# NAPaC.net
KiCad netlist of a schematic drawn in Altium Designer
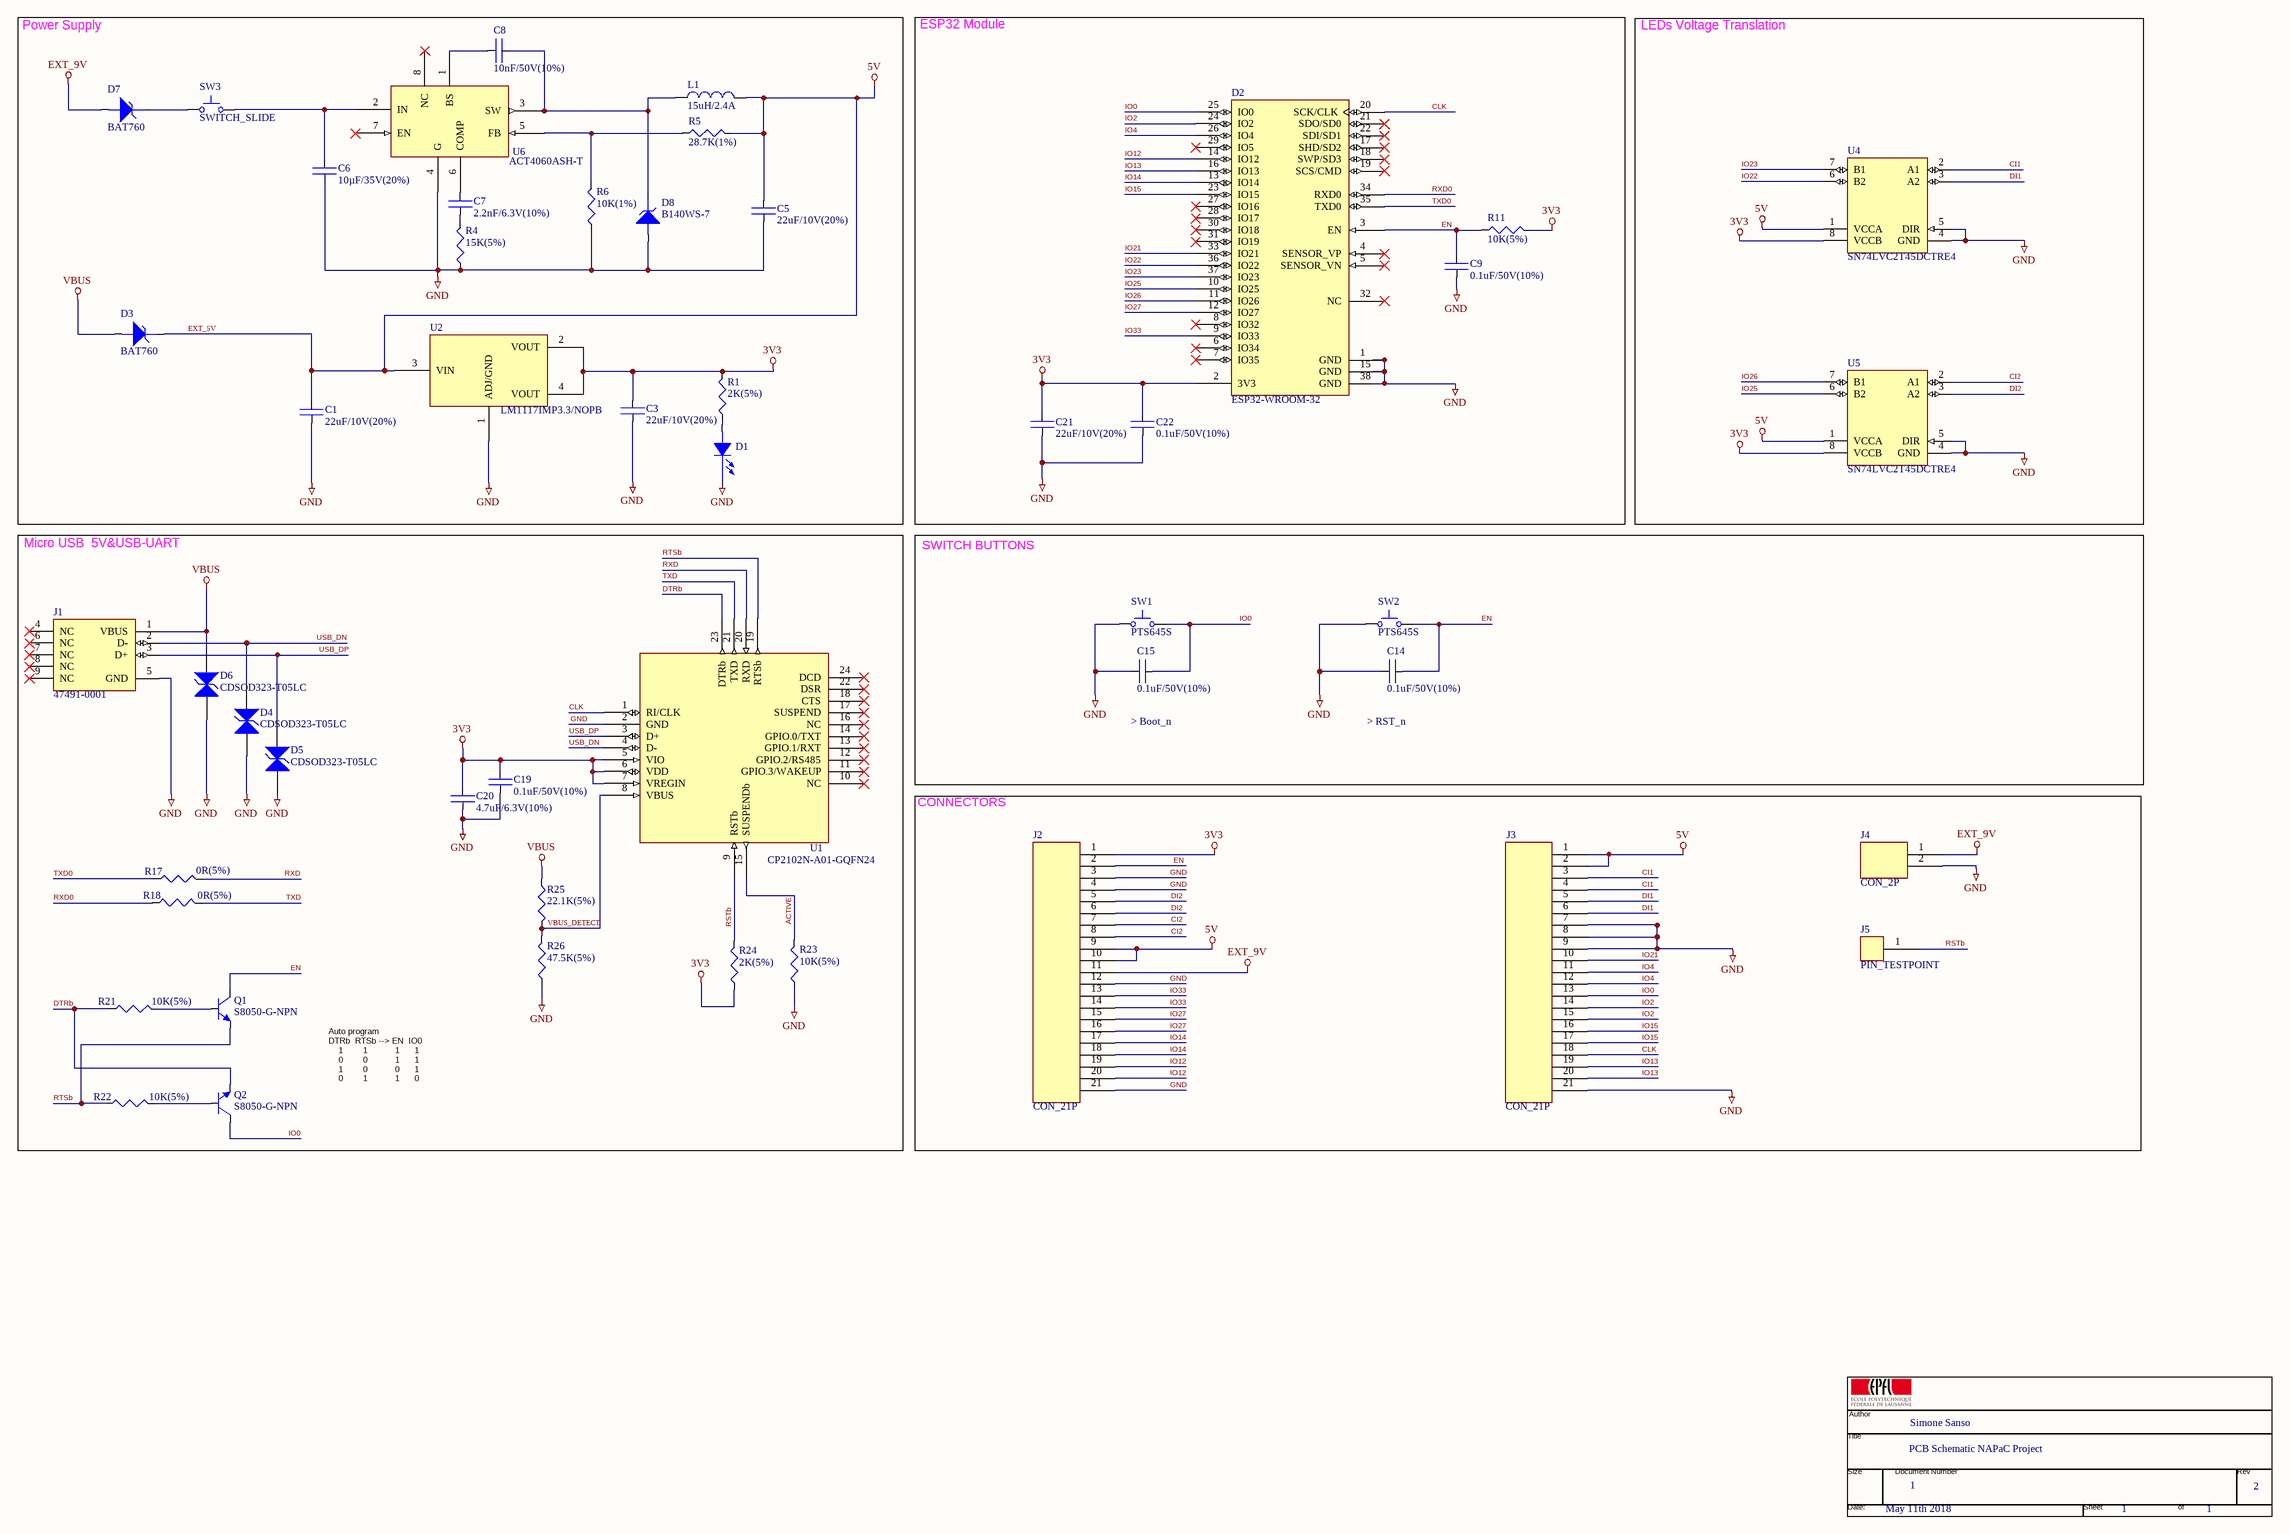
[diagram p0: NAPaC.SchDoc]

(export (version "E")
  (design (tool "Eeschema 10.0.6"))
  (components
    (comp (ref "*") (value "TITLE_BLOCK") (libsource (lib "NAPaC_Schlib") (part "TITLE_BLOCK")))
    (comp (ref "C1")
      (value "22uF/10V(20%)")
      (footprint "CAPC0603")
      (description "GRM188R61A226ME15D-22uF/10V(20%)")
      (libsource (lib "NAPaC_Schlib") (part "CAP-22uF/10V(20%)"))
    )
    (comp (ref "C3")
      (value "22uF/10V(20%)")
      (footprint "CAPC0603")
      (description "GRM188R61A226ME15D-22uF/10V(20%)")
      (libsource (lib "NAPaC_Schlib") (part "CAP-22uF/10V(20%)"))
    )
    (comp (ref "C5")
      (value "22uF/10V(20%)")
      (footprint "CAPC0603")
      (description "GRM188R61A226ME15D-22uF/10V(20%)")
      (libsource (lib "NAPaC_Schlib") (part "CAP-22uF/10V(20%)"))
    )
    (comp (ref "C6")
      (value "10µF/35V(20%)")
      (footprint "CAPC0603")
      (description "C0603C106M8PACTU")
      (libsource (lib "NAPaC_Schlib") (part "CAP-10µF/35V(20%)"))
    )
    (comp (ref "C7")
      (value "2.2nF/6.3V(10%)")
      (footprint "CAPC0603")
      (description "C0603X7R0J222K030BA")
      (libsource (lib "NAPaC_Schlib") (part "CAP-2.2nF/6.3V(10%)"))
    )
    (comp (ref "C8")
      (value "10nF/50V(10%)")
      (footprint "CAPC0603")
      (description "C1608X7R1H103K080AE")
      (libsource (lib "NAPaC_Schlib") (part "CAP-10nF/50V(10%)"))
    )
    (comp (ref "C9")
      (value "0.1uF/50V(10%)")
      (footprint "CAPC0603")
      (description "GRM188R71H104KA93D-0.1uF/50V(10%)")
      (libsource (lib "NAPaC_Schlib") (part "CAP-0.1uF/50V(10%)"))
    )
    (comp (ref "C14")
      (value "0.1uF/50V(10%)")
      (footprint "CAPC0603")
      (description "GRM188R71H104KA93D-0.1uF/50V(10%)")
      (libsource (lib "NAPaC_Schlib") (part "CAP-0.1uF/50V(10%)"))
    )
    (comp (ref "C15")
      (value "0.1uF/50V(10%)")
      (footprint "CAPC0603")
      (description "GRM188R71H104KA93D-0.1uF/50V(10%)")
      (libsource (lib "NAPaC_Schlib") (part "CAP-0.1uF/50V(10%)"))
    )
    (comp (ref "C19")
      (value "0.1uF/50V(10%)")
      (footprint "CAPC0603")
      (description "GRM188R71H104KA93D-0.1uF/50V(10%)")
      (libsource (lib "NAPaC_Schlib") (part "CAP-0.1uF/50V(10%)"))
    )
    (comp (ref "C20")
      (value "4.7uF/6.3V(10%)")
      (footprint "CAPC0603")
      (description "GRT188C80J475KE01D")
      (libsource (lib "NAPaC_Schlib") (part "CAP-0.4uF/6.3V(10%)"))
    )
    (comp (ref "C21")
      (value "22uF/10V(20%)")
      (footprint "CAPC0603")
      (description "GRM188R61A226ME15D-22uF/10V(20%)")
      (libsource (lib "NAPaC_Schlib") (part "CAP-22uF/10V(20%)"))
    )
    (comp (ref "C22")
      (value "0.1uF/50V(10%)")
      (footprint "CAPC0603")
      (description "GRM188R71H104KA93D-0.1uF/50V(10%)")
      (libsource (lib "NAPaC_Schlib") (part "CAP-0.1uF/50V(10%)"))
    )
    (comp (ref "D1")
      (value "SML-D12U1WT86")
      (footprint "SML-D12U1WT86")
      (description "SML-D12U1WT86-2.2V-20mA")
      (libsource (lib "NAPaC_Schlib") (part "RED_LED"))
    )
    (comp (ref "D2")
      (value "ESP32-WROOM-32")
      (footprint "OLMX-ESP-WROOM-32")
      (libsource (lib "NAPaC_Schlib") (part "ESP-WROOM-32"))
    )
    (comp (ref "D3")
      (value "BAT760")
      (footprint "SOD-323")
      (description "BAT760-7-Schottky Diodes & Rectifiers 0.5A 30V LF")
      (libsource (lib "NAPaC_Schlib") (part "SchottkyDiode"))
    )
    (comp (ref "D4")
      (value "CDSOD323-T05LC")
      (footprint "SOD-323")
      (libsource (lib "NAPaC_Schlib") (part "BidirectionalDiode"))
    )
    (comp (ref "D5")
      (value "CDSOD323-T05LC")
      (footprint "SOD-323")
      (libsource (lib "NAPaC_Schlib") (part "BidirectionalDiode"))
    )
    (comp (ref "D6")
      (value "CDSOD323-T05LC")
      (footprint "SOD-323")
      (libsource (lib "NAPaC_Schlib") (part "BidirectionalDiode"))
    )
    (comp (ref "D7")
      (value "BAT760")
      (footprint "SOD-323")
      (description "BAT760-7-Schottky Diodes & Rectifiers 0.5A 30V LF")
      (libsource (lib "NAPaC_Schlib") (part "SchottkyDiode"))
    )
    (comp (ref "D8")
      (value "B140WS-7")
      (footprint "SOD-323-SCHOTTKY_DIODE-40V/1A")
      (description "Diode Schottky 40V 1A 2-Pin SOD-323 T/R")
      (libsource (lib "NAPaC_Schlib") (part "SCHOTTKY_DIODE-40V/3A"))
    )
    (comp (ref "J1")
      (value "47491-0001")
      (footprint "USB-MICRO-B_V")
      (description "USB Connectors MICRO USB B RECPT MIDDLE MNT ASSY")
      (libsource (lib "NAPaC_Schlib") (part "USB_CON8"))
    )
    (comp (ref "J2")
      (value "CON_21P")
      (footprint "PINS_HEADER-21")
      (description "21 Positions Header, Breakaway Connector 0.100\" (2.54mm) Through Hole Tin")
      (libsource (lib "NAPaC_Schlib") (part "PINS_HEADER"))
    )
    (comp (ref "J3")
      (value "CON_21P")
      (footprint "PINS_HEADER-21")
      (description "21 Positions Header, Breakaway Connector 0.100\" (2.54mm) Through Hole Tin")
      (libsource (lib "NAPaC_Schlib") (part "PINS_HEADER"))
    )
    (comp (ref "J4")
      (value "CON_2P")
      (footprint "PINS_ALIM-2")
      (description "2 Positions Header, Breakaway Connector 0.100\" (2.54mm) Through Hole Tin")
      (libsource (lib "NAPaC_Schlib") (part "PIN_ALIM"))
    )
    (comp (ref "J5")
      (value "PIN_TESTPOINT")
      (footprint "PIN_TESTPOINT")
      (description "1 Position Header, Breakaway Connector 0.100\" (2.54mm) Through Hole Tin")
      (libsource (lib "NAPaC_Schlib") (part "PIN_TESTPOINT"))
    )
    (comp (ref "L1")
      (value "15uH/2.4A")
      (footprint "NRS8040-SELF-15uH/2.4A")
      (description "NRS8040T150MJGJ")
      (libsource (lib "NAPaC_Schlib") (part "SELF-15uH/2.4A"))
    )
    (comp (ref "Q1")
      (value "S8050-G-NPN")
      (footprint "SOT23")
      (description "750-SS8050-G-BJT NPN SOT-23-3 TRANSISTOR 1.5A 40V")
      (libsource (lib "NAPaC_Schlib") (part "SS8050-G-NPN"))
    )
    (comp (ref "Q2")
      (value "S8050-G-NPN")
      (description "750-SS8050-G-BJT NPN SOT-23-3 TRANSISTOR 1.5A 40V")
      (libsource (lib "NAPaC_Schlib") (part "SS8050-G-NPNbis"))
    )
    (comp (ref "R1")
      (value "2K(5%)")
      (footprint "RC0402")
      (description "RC0402JR-072KL")
      (libsource (lib "NAPaC_Schlib") (part "RESISTOR-2K(5%)"))
    )
    (comp (ref "R4")
      (value "15K(5%)")
      (footprint "RC0402")
      (description "RC0402JR-7D43KL")
      (libsource (lib "NAPaC_Schlib") (part "RESISTOR-15K(5%)"))
    )
    (comp (ref "R5")
      (value "28.7K(1%)")
      (footprint "RC0402")
      (description "RC0402JR-072K7L")
      (libsource (lib "NAPaC_Schlib") (part "RESISTOR-28.7K(1%)"))
    )
    (comp (ref "R6")
      (value "10K(1%)")
      (footprint "RC0402")
      (description "RC0402F103CS")
      (libsource (lib "NAPaC_Schlib") (part "RESISTOR-10K(1%)"))
    )
    (comp (ref "R11")
      (value "10K(5%)")
      (footprint "RC0402")
      (description "RC0402JR-0710KL")
      (libsource (lib "NAPaC_Schlib") (part "RESISTOR-10K(5%)"))
    )
    (comp (ref "R17")
      (value "0R(5%)")
      (footprint "RC0402")
      (description "RC0402JR-070RL")
      (libsource (lib "NAPaC_Schlib") (part "RESISTOR-0R(5%)"))
    )
    (comp (ref "R18")
      (value "0R(5%)")
      (footprint "RC0402")
      (description "RC0402JR-070RL")
      (libsource (lib "NAPaC_Schlib") (part "RESISTOR-0R(5%)"))
    )
    (comp (ref "R21")
      (value "10K(5%)")
      (footprint "RC0402")
      (description "RC0402JR-0710KL")
      (libsource (lib "NAPaC_Schlib") (part "RESISTOR-10K(5%)"))
    )
    (comp (ref "R22")
      (value "10K(5%)")
      (footprint "RC0402")
      (description "RC0402JR-0710KL")
      (libsource (lib "NAPaC_Schlib") (part "RESISTOR-10K(5%)"))
    )
    (comp (ref "R23")
      (value "10K(5%)")
      (footprint "RC0402")
      (description "RC0402JR-0710KL")
      (libsource (lib "NAPaC_Schlib") (part "RESISTOR-10K(5%)"))
    )
    (comp (ref "R24")
      (value "2K(5%)")
      (footprint "RC0402")
      (description "RC0402JR-072KL")
      (libsource (lib "NAPaC_Schlib") (part "RESISTOR-2K(5%)"))
    )
    (comp (ref "R25")
      (value "22.1K(5%)")
      (footprint "RC0402")
      (description "RC0402FR-0722K1L")
      (libsource (lib "NAPaC_Schlib") (part "RESISTOR-22.1K(5%)"))
    )
    (comp (ref "R26")
      (value "47.5K(5%)")
      (footprint "RC0402")
      (description "RC0402FR-0747K5L")
      (libsource (lib "NAPaC_Schlib") (part "RESISTOR-47.5K(5%)"))
    )
    (comp (ref "SW1")
      (value "PTS645S")
      (footprint "CKCP-PTS645S_V")
      (description "PTS645SL432LFS")
      (libsource (lib "NAPaC_Schlib") (part "SW"))
    )
    (comp (ref "SW2")
      (value "PTS645S")
      (footprint "CKCP-PTS645S_V")
      (description "PTS645SL432LFS")
      (libsource (lib "NAPaC_Schlib") (part "SW"))
    )
    (comp (ref "SW3")
      (value "SWITCH_SLIDE")
      (footprint "SW_SLIDE")
      (description "48ASSP1S1M6QBT")
      (libsource (lib "NAPaC_Schlib") (part "SWITCH_SLIDE"))
    )
    (comp (ref "U1")
      (value "CP2102N-A01-GQFN24")
      (footprint "CP2102N-GQFN24")
      (libsource (lib "NAPaC_Schlib") (part "CP2102N-GQFN24"))
    )
    (comp (ref "U2")
      (value "LM1117IMP3.3/NOPB")
      (footprint "LM1117")
      (libsource (lib "NAPaC_Schlib") (part "LM1117-3.3"))
    )
    (comp (ref "U4")
      (value "SN74LVC2T45DCTRE4")
      (footprint "VOLTAGE_TRANSLATOR_3.3-5V")
      (description "Translation - Voltage Levels DUAL-BIT DUAL SUPPLY TRANSCEIVER")
      (libsource (lib "NAPaC_Schlib") (part "VOLTAGE_TRANSLATOR_3.3-5V"))
    )
    (comp (ref "U5")
      (value "SN74LVC2T45DCTRE4")
      (footprint "VOLTAGE_TRANSLATOR_3.3-5V")
      (description "Translation - Voltage Levels DUAL-BIT DUAL SUPPLY TRANSCEIVER")
      (libsource (lib "NAPaC_Schlib") (part "VOLTAGE_TRANSLATOR_3.3-5V"))
    )
    (comp (ref "U6")
      (value "ACT4060ASH-T")
      (footprint "SWITCHING_VOLTAGE_REGULATOR")
      (libsource (lib "NAPaC_Schlib") (part "SWITCHING_VOLTAGE_REGULATOR"))
    )
  )
  (nets
    (net (code "1") (name "/ACTIVE") (class "Default")
      (node (ref "R23") (pin "2") (pinfunction "2_2") (pintype "passive"))
      (node (ref "U1") (pin "15") (pinfunction "SUSPENDb_15") (pintype "output"))
    )
    (net (code "2") (name "/CI1") (class "Default")
      (node (ref "J3") (pin "3") (pinfunction "1_3") (pintype "passive"))
      (node (ref "J3") (pin "4") (pinfunction "1_4") (pintype "passive"))
      (node (ref "U4") (pin "2") (pinfunction "A1_2") (pintype "bidirectional"))
    )
    (net (code "3") (name "/CI2") (class "Default")
      (node (ref "J2") (pin "7") (pinfunction "1_7") (pintype "passive"))
      (node (ref "J2") (pin "8") (pinfunction "1_8") (pintype "passive"))
      (node (ref "U5") (pin "2") (pinfunction "A1_2") (pintype "bidirectional"))
    )
    (net (code "4") (name "/CLK") (class "Default")
      (node (ref "D2") (pin "20") (pinfunction "SCK/CLK_20") (pintype "bidirectional"))
      (node (ref "J3") (pin "18") (pinfunction "1_18") (pintype "passive"))
      (node (ref "U1") (pin "1") (pinfunction "RI/CLK_1") (pintype "bidirectional"))
    )
    (net (code "5") (name "/DI1") (class "Default")
      (node (ref "J3") (pin "5") (pinfunction "1_5") (pintype "passive"))
      (node (ref "J3") (pin "6") (pinfunction "1_6") (pintype "passive"))
      (node (ref "U4") (pin "3") (pinfunction "A2_3") (pintype "bidirectional"))
    )
    (net (code "6") (name "/DI2") (class "Default")
      (node (ref "J2") (pin "5") (pinfunction "1_5") (pintype "passive"))
      (node (ref "J2") (pin "6") (pinfunction "1_6") (pintype "passive"))
      (node (ref "U5") (pin "3") (pinfunction "A2_3") (pintype "bidirectional"))
    )
    (net (code "7") (name "/DTRb") (class "Default")
      (node (ref "Q2") (pin "2") (pinfunction "EMITTER_2") (pintype "passive"))
      (node (ref "R21") (pin "1") (pinfunction "1_1") (pintype "passive"))
      (node (ref "U1") (pin "23") (pinfunction "DTRb_23") (pintype "output"))
    )
    (net (code "8") (name "/EN") (class "Default")
      (node (ref "C14") (pin "2") (pinfunction "2_2") (pintype "passive"))
      (node (ref "C9") (pin "2") (pinfunction "2_2") (pintype "passive"))
      (node (ref "D2") (pin "3") (pinfunction "EN_3") (pintype "input"))
      (node (ref "J2") (pin "2") (pinfunction "1_2") (pintype "passive"))
      (node (ref "Q1") (pin "3") (pinfunction "COLLECTOR_3") (pintype "passive"))
      (node (ref "R11") (pin "1") (pinfunction "1_1") (pintype "passive"))
      (node (ref "SW2") (pin "2") (pinfunction "2_2") (pintype "passive"))
    )
    (net (code "9") (name "/IO0") (class "Default")
      (node (ref "C15") (pin "2") (pinfunction "2_2") (pintype "passive"))
      (node (ref "D2") (pin "25") (pinfunction "IO0_25") (pintype "bidirectional"))
      (node (ref "J3") (pin "13") (pinfunction "1_13") (pintype "passive"))
      (node (ref "Q2") (pin "3") (pinfunction "COLLECTOR_3") (pintype "passive"))
      (node (ref "SW1") (pin "2") (pinfunction "2_2") (pintype "passive"))
    )
    (net (code "10") (name "/IO2") (class "Default")
      (node (ref "D2") (pin "24") (pinfunction "IO2_24") (pintype "bidirectional"))
      (node (ref "J3") (pin "14") (pinfunction "1_14") (pintype "passive"))
      (node (ref "J3") (pin "15") (pinfunction "1_15") (pintype "passive"))
    )
    (net (code "11") (name "/IO4") (class "Default")
      (node (ref "D2") (pin "26") (pinfunction "IO4_26") (pintype "bidirectional"))
      (node (ref "J3") (pin "11") (pinfunction "1_11") (pintype "passive"))
      (node (ref "J3") (pin "12") (pinfunction "1_12") (pintype "passive"))
    )
    (net (code "12") (name "/IO12") (class "Default")
      (node (ref "D2") (pin "14") (pinfunction "IO12_14") (pintype "bidirectional"))
      (node (ref "J2") (pin "19") (pinfunction "1_19") (pintype "passive"))
      (node (ref "J2") (pin "20") (pinfunction "1_20") (pintype "passive"))
    )
    (net (code "13") (name "/IO13") (class "Default")
      (node (ref "D2") (pin "16") (pinfunction "IO13_16") (pintype "bidirectional"))
      (node (ref "J3") (pin "19") (pinfunction "1_19") (pintype "passive"))
      (node (ref "J3") (pin "20") (pinfunction "1_20") (pintype "passive"))
    )
    (net (code "14") (name "/IO14") (class "Default")
      (node (ref "D2") (pin "13") (pinfunction "IO14_13") (pintype "bidirectional"))
      (node (ref "J2") (pin "17") (pinfunction "1_17") (pintype "passive"))
      (node (ref "J2") (pin "18") (pinfunction "1_18") (pintype "passive"))
    )
    (net (code "15") (name "/IO15") (class "Default")
      (node (ref "D2") (pin "23") (pinfunction "IO15_23") (pintype "bidirectional"))
      (node (ref "J3") (pin "16") (pinfunction "1_16") (pintype "passive"))
      (node (ref "J3") (pin "17") (pinfunction "1_17") (pintype "passive"))
    )
    (net (code "16") (name "/IO21") (class "Default")
      (node (ref "D2") (pin "33") (pinfunction "IO21_33") (pintype "bidirectional"))
      (node (ref "J3") (pin "10") (pinfunction "1_10") (pintype "passive"))
    )
    (net (code "17") (name "/IO22") (class "Default")
      (node (ref "D2") (pin "36") (pinfunction "IO22_36") (pintype "bidirectional"))
      (node (ref "U4") (pin "6") (pinfunction "B2_6") (pintype "bidirectional"))
    )
    (net (code "18") (name "/IO23") (class "Default")
      (node (ref "D2") (pin "37") (pinfunction "IO23_37") (pintype "bidirectional"))
      (node (ref "U4") (pin "7") (pinfunction "B1_7") (pintype "bidirectional"))
    )
    (net (code "19") (name "/IO25") (class "Default")
      (node (ref "D2") (pin "10") (pinfunction "IO25_10") (pintype "bidirectional"))
      (node (ref "U5") (pin "6") (pinfunction "B2_6") (pintype "bidirectional"))
    )
    (net (code "20") (name "/IO26") (class "Default")
      (node (ref "D2") (pin "11") (pinfunction "IO26_11") (pintype "bidirectional"))
      (node (ref "U5") (pin "7") (pinfunction "B1_7") (pintype "bidirectional"))
    )
    (net (code "21") (name "/IO27") (class "Default")
      (node (ref "D2") (pin "12") (pinfunction "IO27_12") (pintype "bidirectional"))
      (node (ref "J2") (pin "15") (pinfunction "1_15") (pintype "passive"))
      (node (ref "J2") (pin "16") (pinfunction "1_16") (pintype "passive"))
    )
    (net (code "22") (name "/IO33") (class "Default")
      (node (ref "D2") (pin "9") (pinfunction "IO33_9") (pintype "bidirectional"))
      (node (ref "J2") (pin "13") (pinfunction "1_13") (pintype "passive"))
      (node (ref "J2") (pin "14") (pinfunction "1_14") (pintype "passive"))
    )
    (net (code "23") (name "/RSTb") (class "Default")
      (node (ref "J5") (pin "1") (pinfunction "Testpoint_1") (pintype "passive"))
      (node (ref "R24") (pin "2") (pinfunction "2_2") (pintype "passive"))
      (node (ref "U1") (pin "9") (pinfunction "RSTb_9") (pintype "input"))
    )
    (net (code "24") (name "/RTSb") (class "Default")
      (node (ref "Q1") (pin "2") (pinfunction "EMITTER_2") (pintype "passive"))
      (node (ref "R22") (pin "1") (pinfunction "1_1") (pintype "passive"))
      (node (ref "U1") (pin "19") (pinfunction "RTSb_19") (pintype "output"))
    )
    (net (code "25") (name "/RXD") (class "Default")
      (node (ref "R17") (pin "2") (pinfunction "2_2") (pintype "passive"))
      (node (ref "U1") (pin "20") (pinfunction "RXD_20") (pintype "input"))
    )
    (net (code "26") (name "/RXD0") (class "Default")
      (node (ref "D2") (pin "34") (pinfunction "RXD0_34") (pintype "bidirectional"))
      (node (ref "R18") (pin "1") (pinfunction "1_1") (pintype "passive"))
    )
    (net (code "27") (name "/TXD") (class "Default")
      (node (ref "R18") (pin "2") (pinfunction "2_2") (pintype "passive"))
      (node (ref "U1") (pin "21") (pinfunction "TXD_21") (pintype "output"))
    )
    (net (code "28") (name "/TXD0") (class "Default")
      (node (ref "D2") (pin "35") (pinfunction "TXD0_35") (pintype "bidirectional"))
      (node (ref "R17") (pin "1") (pinfunction "1_1") (pintype "passive"))
    )
    (net (code "29") (name "/USB_DN") (class "Default")
      (node (ref "D4") (pin "2") (pinfunction "C_2") (pintype "passive"))
      (node (ref "J1") (pin "2") (pinfunction "D-_2") (pintype "bidirectional"))
      (node (ref "U1") (pin "4") (pinfunction "D-_4") (pintype "bidirectional"))
    )
    (net (code "30") (name "/USB_DP") (class "Default")
      (node (ref "D5") (pin "2") (pinfunction "C_2") (pintype "passive"))
      (node (ref "J1") (pin "3") (pinfunction "D+_3") (pintype "bidirectional"))
      (node (ref "U1") (pin "3") (pinfunction "D+_3") (pintype "bidirectional"))
    )
    (net (code "31") (name "/VBUS_DETECT") (class "Default")
      (node (ref "R25") (pin "2") (pinfunction "2_2") (pintype "passive"))
      (node (ref "R26") (pin "2") (pinfunction "2_2") (pintype "passive"))
      (node (ref "U1") (pin "8") (pinfunction "VBUS_8") (pintype "input"))
    )
    (net (code "32") (name "3V3") (class "Default")
      (node (ref "C19") (pin "2") (pinfunction "2_2") (pintype "passive"))
      (node (ref "C20") (pin "2") (pinfunction "2_2") (pintype "passive"))
      (node (ref "C21") (pin "2") (pinfunction "2_2") (pintype "passive"))
      (node (ref "C22") (pin "2") (pinfunction "2_2") (pintype "passive"))
      (node (ref "C3") (pin "2") (pinfunction "2_2") (pintype "passive"))
      (node (ref "D2") (pin "2") (pinfunction "3V3_2") (pintype "power_in"))
      (node (ref "J2") (pin "1") (pinfunction "1_1") (pintype "passive"))
      (node (ref "R1") (pin "2") (pinfunction "2_2") (pintype "passive"))
      (node (ref "R11") (pin "2") (pinfunction "2_2") (pintype "passive"))
      (node (ref "R24") (pin "1") (pinfunction "1_1") (pintype "passive"))
      (node (ref "U1") (pin "5") (pinfunction "VIO_5") (pintype "input"))
      (node (ref "U1") (pin "6") (pinfunction "VDD_6") (pintype "bidirectional"))
      (node (ref "U1") (pin "7") (pinfunction "VREGIN_7") (pintype "input"))
      (node (ref "U2") (pin "2") (pinfunction "VOUT_2") (pintype "power_in"))
      (node (ref "U2") (pin "4") (pinfunction "VOUT_4") (pintype "power_in"))
      (node (ref "U4") (pin "8") (pinfunction "VCCB_8") (pintype "power_in"))
      (node (ref "U5") (pin "8") (pinfunction "VCCB_8") (pintype "power_in"))
    )
    (net (code "33") (name "5V") (class "Default")
      (node (ref "C1") (pin "2") (pinfunction "2_2") (pintype "passive"))
      (node (ref "C5") (pin "2") (pinfunction "2_2") (pintype "passive"))
      (node (ref "D3") (pin "2") (pinfunction "K_2") (pintype "passive"))
      (node (ref "J2") (pin "10") (pinfunction "1_10") (pintype "passive"))
      (node (ref "J2") (pin "9") (pinfunction "1_9") (pintype "passive"))
      (node (ref "J3") (pin "1") (pinfunction "1_1") (pintype "passive"))
      (node (ref "J3") (pin "2") (pinfunction "1_2") (pintype "passive"))
      (node (ref "L1") (pin "2") (pinfunction "2_2") (pintype "passive"))
      (node (ref "R5") (pin "2") (pinfunction "2_2") (pintype "passive"))
      (node (ref "U2") (pin "3") (pinfunction "VIN_3") (pintype "power_in"))
      (node (ref "U4") (pin "1") (pinfunction "VCCA_1") (pintype "power_in"))
      (node (ref "U5") (pin "1") (pinfunction "VCCA_1") (pintype "power_in"))
    )
    (net (code "34") (name "EXT_9V") (class "Default")
      (node (ref "D7") (pin "1") (pinfunction "A_1") (pintype "passive"))
      (node (ref "J2") (pin "11") (pinfunction "1_11") (pintype "passive"))
      (node (ref "J4") (pin "1") (pinfunction "VIN_1") (pintype "power_in"))
    )
    (net (code "35") (name "GND") (class "Default")
      (node (ref "C1") (pin "1") (pinfunction "1_1") (pintype "passive"))
      (node (ref "C14") (pin "1") (pinfunction "1_1") (pintype "passive"))
      (node (ref "C15") (pin "1") (pinfunction "1_1") (pintype "passive"))
      (node (ref "C19") (pin "1") (pinfunction "1_1") (pintype "passive"))
      (node (ref "C20") (pin "1") (pinfunction "1_1") (pintype "passive"))
      (node (ref "C21") (pin "1") (pinfunction "1_1") (pintype "passive"))
      (node (ref "C22") (pin "1") (pinfunction "1_1") (pintype "passive"))
      (node (ref "C3") (pin "1") (pinfunction "1_1") (pintype "passive"))
      (node (ref "C5") (pin "1") (pinfunction "1_1") (pintype "passive"))
      (node (ref "C6") (pin "1") (pinfunction "1_1") (pintype "passive"))
      (node (ref "C9") (pin "1") (pinfunction "1_1") (pintype "passive"))
      (node (ref "D1") (pin "2") (pinfunction "2_2") (pintype "passive"))
      (node (ref "D2") (pin "1") (pinfunction "GND_1") (pintype "power_in"))
      (node (ref "D2") (pin "15") (pinfunction "GND_15") (pintype "power_in"))
      (node (ref "D2") (pin "38") (pinfunction "GND_38") (pintype "power_in"))
      (node (ref "D4") (pin "1") (pinfunction "C_1") (pintype "passive"))
      (node (ref "D5") (pin "1") (pinfunction "C_1") (pintype "passive"))
      (node (ref "D6") (pin "1") (pinfunction "C_1") (pintype "passive"))
      (node (ref "D8") (pin "1") (pinfunction "A_1") (pintype "passive"))
      (node (ref "J1") (pin "5") (pinfunction "GND_5") (pintype "power_in"))
      (node (ref "J2") (pin "12") (pinfunction "1_12") (pintype "passive"))
      (node (ref "J2") (pin "21") (pinfunction "1_21") (pintype "passive"))
      (node (ref "J2") (pin "3") (pinfunction "1_3") (pintype "passive"))
      (node (ref "J2") (pin "4") (pinfunction "1_4") (pintype "passive"))
      (node (ref "J3") (pin "21") (pinfunction "1_21") (pintype "passive"))
      (node (ref "J3") (pin "7") (pinfunction "1_7") (pintype "passive"))
      (node (ref "J3") (pin "8") (pinfunction "1_8") (pintype "passive"))
      (node (ref "J3") (pin "9") (pinfunction "1_9") (pintype "passive"))
      (node (ref "J4") (pin "2") (pinfunction "GND_2") (pintype "passive"))
      (node (ref "R23") (pin "1") (pinfunction "1_1") (pintype "passive"))
      (node (ref "R26") (pin "1") (pinfunction "1_1") (pintype "passive"))
      (node (ref "R4") (pin "1") (pinfunction "1_1") (pintype "passive"))
      (node (ref "R6") (pin "1") (pinfunction "1_1") (pintype "passive"))
      (node (ref "SW1") (pin "1") (pinfunction "1_1") (pintype "passive"))
      (node (ref "SW2") (pin "1") (pinfunction "1_1") (pintype "passive"))
      (node (ref "U1") (pin "2") (pinfunction "GND_2") (pintype "passive"))
      (node (ref "U2") (pin "1") (pinfunction "ADJ/GND_1") (pintype "passive"))
      (node (ref "U4") (pin "4") (pinfunction "GND_4") (pintype "power_in"))
      (node (ref "U4") (pin "5") (pinfunction "DIR_5") (pintype "input"))
      (node (ref "U5") (pin "4") (pinfunction "GND_4") (pintype "power_in"))
      (node (ref "U5") (pin "5") (pinfunction "DIR_5") (pintype "input"))
      (node (ref "U6") (pin "4") (pinfunction "G_4") (pintype "power_in"))
    )
    (net (code "36") (name "Net-(C7-Pad1)") (class "Default")
      (node (ref "C7") (pin "1") (pinfunction "1_1") (pintype "passive"))
      (node (ref "R4") (pin "2") (pinfunction "2_2") (pintype "passive"))
    )
    (net (code "37") (name "Net-(D1-Pad1)") (class "Default")
      (node (ref "D1") (pin "1") (pinfunction "1_1") (pintype "passive"))
      (node (ref "R1") (pin "1") (pinfunction "1_1") (pintype "passive"))
    )
    (net (code "38") (name "Net-(D7-K)") (class "Default")
      (node (ref "D7") (pin "2") (pinfunction "K_2") (pintype "passive"))
      (node (ref "SW3") (pin "1") (pinfunction "1_1") (pintype "passive"))
    )
    (net (code "39") (name "Net-(D8-K)") (class "Default")
      (node (ref "C8") (pin "2") (pinfunction "2_2") (pintype "passive"))
      (node (ref "D8") (pin "2") (pinfunction "K_2") (pintype "passive"))
      (node (ref "L1") (pin "1") (pinfunction "1_1") (pintype "passive"))
      (node (ref "U6") (pin "3") (pinfunction "SW_3") (pintype "output"))
    )
    (net (code "40") (name "Net-(Q1-BASE)") (class "Default")
      (node (ref "Q1") (pin "1") (pinfunction "BASE_1") (pintype "passive"))
      (node (ref "R21") (pin "2") (pinfunction "2_2") (pintype "passive"))
    )
    (net (code "41") (name "Net-(Q2-BASE)") (class "Default")
      (node (ref "Q2") (pin "1") (pinfunction "BASE_1") (pintype "passive"))
      (node (ref "R22") (pin "2") (pinfunction "2_2") (pintype "passive"))
    )
    (net (code "42") (name "Net-(U6-BS)") (class "Default")
      (node (ref "C8") (pin "1") (pinfunction "1_1") (pintype "passive"))
      (node (ref "U6") (pin "1") (pinfunction "BS_1") (pintype "passive"))
    )
    (net (code "43") (name "Net-(U6-COMP)") (class "Default")
      (node (ref "C7") (pin "2") (pinfunction "2_2") (pintype "passive"))
      (node (ref "U6") (pin "6") (pinfunction "COMP_6") (pintype "passive"))
    )
    (net (code "44") (name "Net-(U6-FB)") (class "Default")
      (node (ref "R5") (pin "1") (pinfunction "1_1") (pintype "passive"))
      (node (ref "R6") (pin "2") (pinfunction "2_2") (pintype "passive"))
      (node (ref "U6") (pin "5") (pinfunction "FB_5") (pintype "input"))
    )
    (net (code "45") (name "Net-(U6-IN)") (class "Default")
      (node (ref "C6") (pin "2") (pinfunction "2_2") (pintype "passive"))
      (node (ref "SW3") (pin "2") (pinfunction "2_2") (pintype "passive"))
      (node (ref "U6") (pin "2") (pinfunction "IN_2") (pintype "power_in"))
    )
    (net (code "46") (name "VBUS") (class "Default")
      (node (ref "D3") (pin "1") (pinfunction "A_1") (pintype "passive"))
      (node (ref "D6") (pin "2") (pinfunction "C_2") (pintype "passive"))
      (node (ref "J1") (pin "1") (pinfunction "VBUS_1") (pintype "power_in"))
      (node (ref "R25") (pin "1") (pinfunction "1_1") (pintype "passive"))
    )
    (net (code "47") (name "unconnected-(D2-IO5-Pad29)") (class "Default")
      (node (ref "D2") (pin "29") (pinfunction "IO5_29") (pintype "bidirectional+no_connect"))
    )
    (net (code "48") (name "unconnected-(D2-IO16-Pad27)") (class "Default")
      (node (ref "D2") (pin "27") (pinfunction "IO16_27") (pintype "bidirectional+no_connect"))
    )
    (net (code "49") (name "unconnected-(D2-IO17-Pad28)") (class "Default")
      (node (ref "D2") (pin "28") (pinfunction "IO17_28") (pintype "bidirectional+no_connect"))
    )
    (net (code "50") (name "unconnected-(D2-IO18-Pad30)") (class "Default")
      (node (ref "D2") (pin "30") (pinfunction "IO18_30") (pintype "bidirectional+no_connect"))
    )
    (net (code "51") (name "unconnected-(D2-IO19-Pad31)") (class "Default")
      (node (ref "D2") (pin "31") (pinfunction "IO19_31") (pintype "bidirectional+no_connect"))
    )
    (net (code "52") (name "unconnected-(D2-IO32-Pad8)") (class "Default")
      (node (ref "D2") (pin "8") (pinfunction "IO32_8") (pintype "bidirectional+no_connect"))
    )
    (net (code "53") (name "unconnected-(D2-IO34-Pad6)") (class "Default")
      (node (ref "D2") (pin "6") (pinfunction "IO34_6") (pintype "bidirectional+no_connect"))
    )
    (net (code "54") (name "unconnected-(D2-IO35-Pad7)") (class "Default")
      (node (ref "D2") (pin "7") (pinfunction "IO35_7") (pintype "bidirectional+no_connect"))
    )
    (net (code "55") (name "unconnected-(D2-NC-Pad32)") (class "Default")
      (node (ref "D2") (pin "32") (pinfunction "NC_32") (pintype "passive+no_connect"))
    )
    (net (code "56") (name "unconnected-(D2-SCS{slash}CMD-Pad19)") (class "Default")
      (node (ref "D2") (pin "19") (pinfunction "SCS/CMD_19") (pintype "bidirectional+no_connect"))
    )
    (net (code "57") (name "unconnected-(D2-SDI{slash}SD1-Pad22)") (class "Default")
      (node (ref "D2") (pin "22") (pinfunction "SDI/SD1_22") (pintype "bidirectional+no_connect"))
    )
    (net (code "58") (name "unconnected-(D2-SDO{slash}SD0-Pad21)") (class "Default")
      (node (ref "D2") (pin "21") (pinfunction "SDO/SD0_21") (pintype "bidirectional+no_connect"))
    )
    (net (code "59") (name "unconnected-(D2-SENSOR_VN-Pad5)") (class "Default")
      (node (ref "D2") (pin "5") (pinfunction "SENSOR_VN_5") (pintype "input+no_connect"))
    )
    (net (code "60") (name "unconnected-(D2-SENSOR_VP-Pad4)") (class "Default")
      (node (ref "D2") (pin "4") (pinfunction "SENSOR_VP_4") (pintype "input+no_connect"))
    )
    (net (code "61") (name "unconnected-(D2-SHD{slash}SD2-Pad17)") (class "Default")
      (node (ref "D2") (pin "17") (pinfunction "SHD/SD2_17") (pintype "bidirectional+no_connect"))
    )
    (net (code "62") (name "unconnected-(D2-SWP{slash}SD3-Pad18)") (class "Default")
      (node (ref "D2") (pin "18") (pinfunction "SWP/SD3_18") (pintype "bidirectional+no_connect"))
    )
    (net (code "63") (name "unconnected-(J1-NC-Pad4)") (class "Default")
      (node (ref "J1") (pin "4") (pinfunction "NC_4") (pintype "passive+no_connect"))
    )
    (net (code "64") (name "unconnected-(J1-NC-Pad6)") (class "Default")
      (node (ref "J1") (pin "6") (pinfunction "NC_6") (pintype "passive+no_connect"))
    )
    (net (code "65") (name "unconnected-(J1-NC-Pad7)") (class "Default")
      (node (ref "J1") (pin "7") (pinfunction "NC_7") (pintype "passive+no_connect"))
    )
    (net (code "66") (name "unconnected-(J1-NC-Pad8)") (class "Default")
      (node (ref "J1") (pin "8") (pinfunction "NC_8") (pintype "passive+no_connect"))
    )
    (net (code "67") (name "unconnected-(J1-NC-Pad9)") (class "Default")
      (node (ref "J1") (pin "9") (pinfunction "NC_9") (pintype "passive+no_connect"))
    )
    (net (code "68") (name "unconnected-(U1-CTS-Pad18)") (class "Default")
      (node (ref "U1") (pin "18") (pinfunction "CTS_18") (pintype "passive+no_connect"))
    )
    (net (code "69") (name "unconnected-(U1-DCD-Pad24)") (class "Default")
      (node (ref "U1") (pin "24") (pinfunction "DCD_24") (pintype "passive+no_connect"))
    )
    (net (code "70") (name "unconnected-(U1-DSR-Pad22)") (class "Default")
      (node (ref "U1") (pin "22") (pinfunction "DSR_22") (pintype "passive+no_connect"))
    )
    (net (code "71") (name "unconnected-(U1-GPIO.0{slash}TXT-Pad14)") (class "Default")
      (node (ref "U1") (pin "14") (pinfunction "GPIO.0/TXT_14") (pintype "passive+no_connect"))
    )
    (net (code "72") (name "unconnected-(U1-GPIO.1{slash}RXT-Pad13)") (class "Default")
      (node (ref "U1") (pin "13") (pinfunction "GPIO.1/RXT_13") (pintype "passive+no_connect"))
    )
    (net (code "73") (name "unconnected-(U1-GPIO.2{slash}RS485-Pad12)") (class "Default")
      (node (ref "U1") (pin "12") (pinfunction "GPIO.2/RS485_12") (pintype "passive+no_connect"))
    )
    (net (code "74") (name "unconnected-(U1-GPIO.3{slash}WAKEUP-Pad11)") (class "Default")
      (node (ref "U1") (pin "11") (pinfunction "GPIO.3/WAKEUP_11") (pintype "passive+no_connect"))
    )
    (net (code "75") (name "unconnected-(U1-NC-Pad10)") (class "Default")
      (node (ref "U1") (pin "10") (pinfunction "NC_10") (pintype "passive+no_connect"))
    )
    (net (code "76") (name "unconnected-(U1-NC-Pad16)") (class "Default")
      (node (ref "U1") (pin "16") (pinfunction "NC_16") (pintype "passive+no_connect"))
    )
    (net (code "77") (name "unconnected-(U1-SUSPEND-Pad17)") (class "Default")
      (node (ref "U1") (pin "17") (pinfunction "SUSPEND_17") (pintype "passive+no_connect"))
    )
    (net (code "78") (name "unconnected-(U6-EN-Pad7)") (class "Default")
      (node (ref "U6") (pin "7") (pinfunction "EN_7") (pintype "input+no_connect"))
    )
    (net (code "79") (name "unconnected-(U6-NC-Pad8)") (class "Default")
      (node (ref "U6") (pin "8") (pinfunction "NC_8") (pintype "passive+no_connect"))
    )
  )
)
